# trig_board.net
KiCad netlist of a schematic drawn in EAGLE
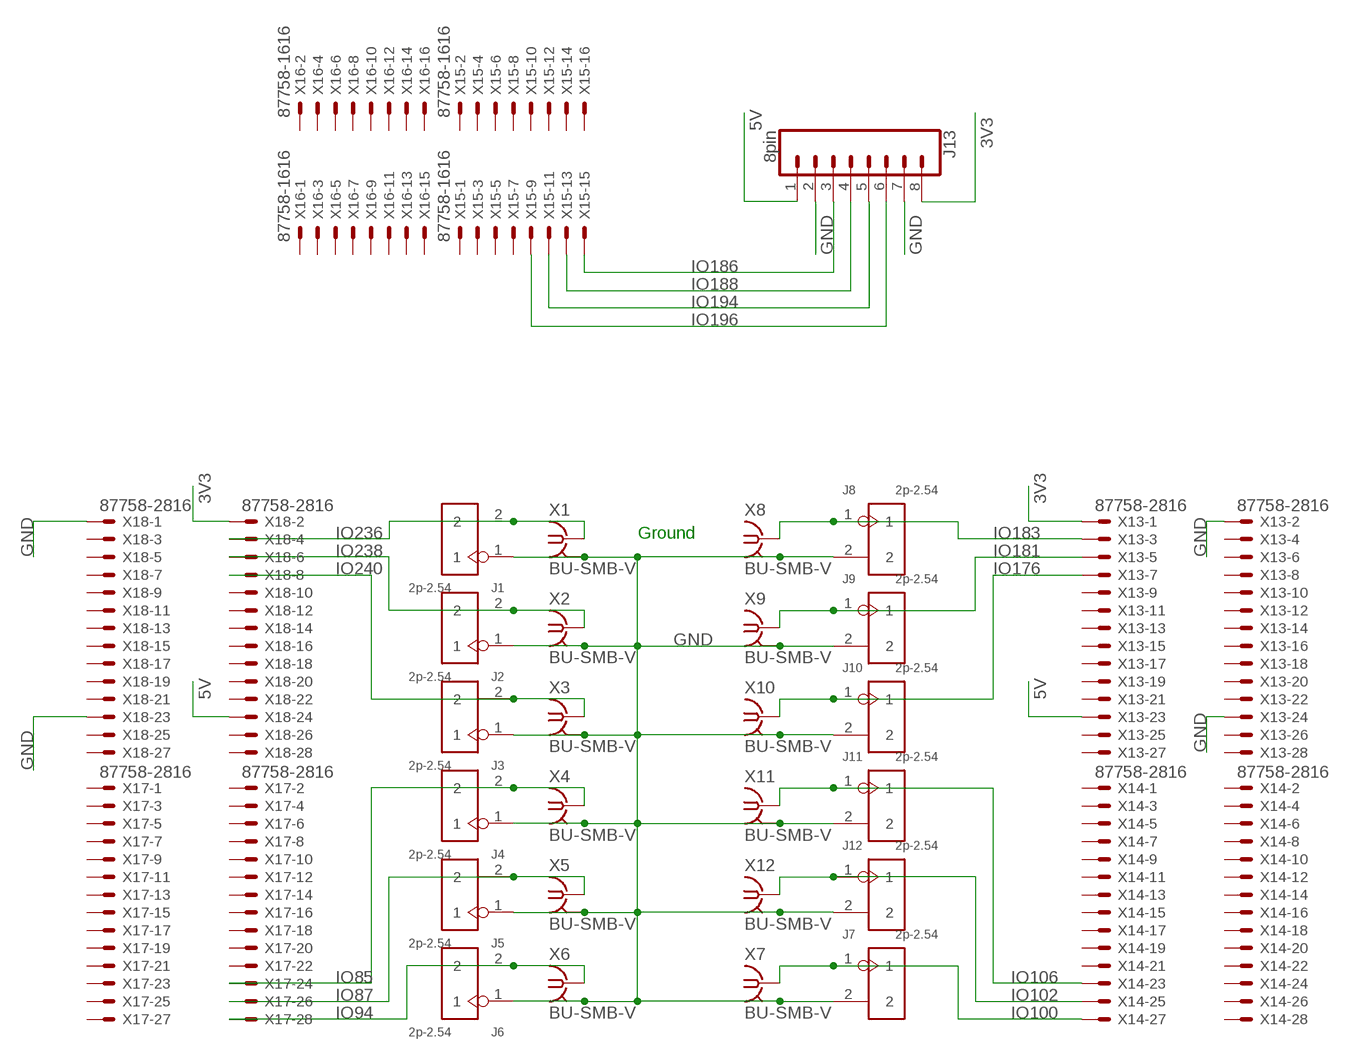
[diagram p0: schematic, sheet 1]

(export (version "E")
  (design (tool "Eeschema 10.0.6"))
  (components
    (comp (ref "J1")
      (value "2p-2.54")
      (footprint "eagle-import:H2-2.54")
      (fields (field (name "MPN") "P125-1102A0BS116A1"))
      (libsource (lib "eagle-import") (part "DIP-BLACK-MALE-HEADER-VERT(2P-2.54)"))
    )
    (comp (ref "J2")
      (value "2p-2.54")
      (footprint "eagle-import:H2-2.54")
      (fields (field (name "MPN") "P125-1102A0BS116A1"))
      (libsource (lib "eagle-import") (part "DIP-BLACK-MALE-HEADER-VERT(2P-2.54)"))
    )
    (comp (ref "J3")
      (value "2p-2.54")
      (footprint "eagle-import:H2-2.54")
      (fields (field (name "MPN") "P125-1102A0BS116A1"))
      (libsource (lib "eagle-import") (part "DIP-BLACK-MALE-HEADER-VERT(2P-2.54)"))
    )
    (comp (ref "J4")
      (value "2p-2.54")
      (footprint "eagle-import:H2-2.54")
      (fields (field (name "MPN") "P125-1102A0BS116A1"))
      (libsource (lib "eagle-import") (part "DIP-BLACK-MALE-HEADER-VERT(2P-2.54)"))
    )
    (comp (ref "J5")
      (value "2p-2.54")
      (footprint "eagle-import:H2-2.54")
      (fields (field (name "MPN") "P125-1102A0BS116A1"))
      (libsource (lib "eagle-import") (part "DIP-BLACK-MALE-HEADER-VERT(2P-2.54)"))
    )
    (comp (ref "J6")
      (value "2p-2.54")
      (footprint "eagle-import:H2-2.54")
      (fields (field (name "MPN") "P125-1102A0BS116A1"))
      (libsource (lib "eagle-import") (part "DIP-BLACK-MALE-HEADER-VERT(2P-2.54)"))
    )
    (comp (ref "J7")
      (value "2p-2.54")
      (footprint "eagle-import:H2-2.54")
      (fields (field (name "MPN") "P125-1102A0BS116A1"))
      (libsource (lib "eagle-import") (part "DIP-BLACK-MALE-HEADER-VERT(2P-2.54)"))
    )
    (comp (ref "J8")
      (value "2p-2.54")
      (footprint "eagle-import:H2-2.54")
      (fields (field (name "MPN") "P125-1102A0BS116A1"))
      (libsource (lib "eagle-import") (part "DIP-BLACK-MALE-HEADER-VERT(2P-2.54)"))
    )
    (comp (ref "J9")
      (value "2p-2.54")
      (footprint "eagle-import:H2-2.54")
      (fields (field (name "MPN") "P125-1102A0BS116A1"))
      (libsource (lib "eagle-import") (part "DIP-BLACK-MALE-HEADER-VERT(2P-2.54)"))
    )
    (comp (ref "J10")
      (value "2p-2.54")
      (footprint "eagle-import:H2-2.54")
      (fields (field (name "MPN") "P125-1102A0BS116A1"))
      (libsource (lib "eagle-import") (part "DIP-BLACK-MALE-HEADER-VERT(2P-2.54)"))
    )
    (comp (ref "J11")
      (value "2p-2.54")
      (footprint "eagle-import:H2-2.54")
      (fields (field (name "MPN") "P125-1102A0BS116A1"))
      (libsource (lib "eagle-import") (part "DIP-BLACK-MALE-HEADER-VERT(2P-2.54)"))
    )
    (comp (ref "J12")
      (value "2p-2.54")
      (footprint "eagle-import:H2-2.54")
      (fields (field (name "MPN") "P125-1102A0BS116A1"))
      (libsource (lib "eagle-import") (part "DIP-BLACK-MALE-HEADER-VERT(2P-2.54)"))
    )
    (comp (ref "J13")
      (value "8pin")
      (footprint "eagle-import:1X08")
      (libsource (lib "eagle-import") (part "CONN_08{dblquote}"))
    )
    (comp (ref "X1")
      (value "BU-SMB-V")
      (footprint "eagle-import:BU-SMB-V")
      (libsource (lib "eagle-import") (part "BU-SMB-V"))
    )
    (comp (ref "X2")
      (value "BU-SMB-V")
      (footprint "eagle-import:BU-SMB-V")
      (libsource (lib "eagle-import") (part "BU-SMB-V"))
    )
    (comp (ref "X3")
      (value "BU-SMB-V")
      (footprint "eagle-import:BU-SMB-V")
      (libsource (lib "eagle-import") (part "BU-SMB-V"))
    )
    (comp (ref "X4")
      (value "BU-SMB-V")
      (footprint "eagle-import:BU-SMB-V")
      (libsource (lib "eagle-import") (part "BU-SMB-V"))
    )
    (comp (ref "X5")
      (value "BU-SMB-V")
      (footprint "eagle-import:BU-SMB-V")
      (libsource (lib "eagle-import") (part "BU-SMB-V"))
    )
    (comp (ref "X6")
      (value "BU-SMB-V")
      (footprint "eagle-import:BU-SMB-V")
      (libsource (lib "eagle-import") (part "BU-SMB-V"))
    )
    (comp (ref "X7")
      (value "BU-SMB-V")
      (footprint "eagle-import:BU-SMB-V")
      (libsource (lib "eagle-import") (part "BU-SMB-V"))
    )
    (comp (ref "X8")
      (value "BU-SMB-V")
      (footprint "eagle-import:BU-SMB-V")
      (libsource (lib "eagle-import") (part "BU-SMB-V"))
    )
    (comp (ref "X9")
      (value "BU-SMB-V")
      (footprint "eagle-import:BU-SMB-V")
      (libsource (lib "eagle-import") (part "BU-SMB-V"))
    )
    (comp (ref "X10")
      (value "BU-SMB-V")
      (footprint "eagle-import:BU-SMB-V")
      (libsource (lib "eagle-import") (part "BU-SMB-V"))
    )
    (comp (ref "X11")
      (value "BU-SMB-V")
      (footprint "eagle-import:BU-SMB-V")
      (libsource (lib "eagle-import") (part "BU-SMB-V"))
    )
    (comp (ref "X12")
      (value "BU-SMB-V")
      (footprint "eagle-import:BU-SMB-V")
      (libsource (lib "eagle-import") (part "BU-SMB-V"))
    )
    (comp (ref "X13")
      (value "87758-2816")
      (footprint "eagle-import:87758-2816")
      (fields (field (name "MF") "MOLEX"))
      (libsource (lib "eagle-import") (part "87758-2816"))
    )
    (comp (ref "X14")
      (value "87758-2816")
      (footprint "eagle-import:87758-2816")
      (fields (field (name "MF") "MOLEX"))
      (libsource (lib "eagle-import") (part "87758-2816"))
    )
    (comp (ref "X15")
      (value "87758-1616")
      (footprint "eagle-import:87758-1616")
      (fields (field (name "MF") "MOLEX"))
      (libsource (lib "eagle-import") (part "87758-1616"))
    )
    (comp (ref "X16")
      (value "87758-1616")
      (footprint "eagle-import:87758-1616")
      (fields (field (name "MF") "MOLEX"))
      (libsource (lib "eagle-import") (part "87758-1616"))
    )
    (comp (ref "X17")
      (value "87758-2816")
      (footprint "eagle-import:87758-2816")
      (fields (field (name "MF") "MOLEX"))
      (libsource (lib "eagle-import") (part "87758-2816"))
    )
    (comp (ref "X18")
      (value "87758-2816")
      (footprint "eagle-import:87758-2816")
      (fields (field (name "MF") "MOLEX"))
      (libsource (lib "eagle-import") (part "87758-2816"))
    )
  )
  (nets
    (net (code "1") (name "/3V3") (class "Default")
      (node (ref "J13") (pin "8") (pinfunction "8_8") (pintype "passive"))
      (node (ref "X13") (pin "1") (pinfunction "S_1") (pintype "passive"))
      (node (ref "X18") (pin "2") (pinfunction "S_2") (pintype "passive"))
    )
    (net (code "2") (name "/5V") (class "Default")
      (node (ref "J13") (pin "1") (pinfunction "1_1") (pintype "passive"))
      (node (ref "X13") (pin "23") (pinfunction "S_23") (pintype "passive"))
      (node (ref "X18") (pin "24") (pinfunction "S_24") (pintype "passive"))
    )
    (net (code "3") (name "/GND") (class "Default")
      (node (ref "J1") (pin "1") (pinfunction "1_1") (pintype "bidirectional"))
      (node (ref "J10") (pin "2") (pinfunction "2_2") (pintype "bidirectional"))
      (node (ref "J11") (pin "2") (pinfunction "2_2") (pintype "bidirectional"))
      (node (ref "J12") (pin "2") (pinfunction "2_2") (pintype "bidirectional"))
      (node (ref "J13") (pin "2") (pinfunction "2_2") (pintype "passive"))
      (node (ref "J13") (pin "7") (pinfunction "7_7") (pintype "passive"))
      (node (ref "J2") (pin "1") (pinfunction "1_1") (pintype "bidirectional"))
      (node (ref "J3") (pin "1") (pinfunction "1_1") (pintype "bidirectional"))
      (node (ref "J4") (pin "1") (pinfunction "1_1") (pintype "bidirectional"))
      (node (ref "J5") (pin "1") (pinfunction "1_1") (pintype "bidirectional"))
      (node (ref "J6") (pin "1") (pinfunction "1_1") (pintype "bidirectional"))
      (node (ref "J7") (pin "2") (pinfunction "2_2") (pintype "bidirectional"))
      (node (ref "J8") (pin "2") (pinfunction "2_2") (pintype "bidirectional"))
      (node (ref "J9") (pin "2") (pinfunction "2_2") (pintype "bidirectional"))
      (node (ref "X1") (pin "2") (pinfunction "2_2") (pintype "passive"))
      (node (ref "X1") (pin "3") (pinfunction "2_3") (pintype "passive"))
      (node (ref "X1") (pin "4") (pinfunction "2_4") (pintype "passive"))
      (node (ref "X1") (pin "5") (pinfunction "2_5") (pintype "passive"))
      (node (ref "X10") (pin "2") (pinfunction "2_2") (pintype "passive"))
      (node (ref "X10") (pin "3") (pinfunction "2_3") (pintype "passive"))
      (node (ref "X10") (pin "4") (pinfunction "2_4") (pintype "passive"))
      (node (ref "X10") (pin "5") (pinfunction "2_5") (pintype "passive"))
      (node (ref "X11") (pin "2") (pinfunction "2_2") (pintype "passive"))
      (node (ref "X11") (pin "3") (pinfunction "2_3") (pintype "passive"))
      (node (ref "X11") (pin "4") (pinfunction "2_4") (pintype "passive"))
      (node (ref "X11") (pin "5") (pinfunction "2_5") (pintype "passive"))
      (node (ref "X12") (pin "2") (pinfunction "2_2") (pintype "passive"))
      (node (ref "X12") (pin "3") (pinfunction "2_3") (pintype "passive"))
      (node (ref "X12") (pin "4") (pinfunction "2_4") (pintype "passive"))
      (node (ref "X12") (pin "5") (pinfunction "2_5") (pintype "passive"))
      (node (ref "X13") (pin "2") (pinfunction "S_2") (pintype "passive"))
      (node (ref "X13") (pin "24") (pinfunction "S_24") (pintype "passive"))
      (node (ref "X18") (pin "1") (pinfunction "S_1") (pintype "passive"))
      (node (ref "X18") (pin "23") (pinfunction "S_23") (pintype "passive"))
      (node (ref "X2") (pin "2") (pinfunction "2_2") (pintype "passive"))
      (node (ref "X2") (pin "3") (pinfunction "2_3") (pintype "passive"))
      (node (ref "X2") (pin "4") (pinfunction "2_4") (pintype "passive"))
      (node (ref "X2") (pin "5") (pinfunction "2_5") (pintype "passive"))
      (node (ref "X3") (pin "2") (pinfunction "2_2") (pintype "passive"))
      (node (ref "X3") (pin "3") (pinfunction "2_3") (pintype "passive"))
      (node (ref "X3") (pin "4") (pinfunction "2_4") (pintype "passive"))
      (node (ref "X3") (pin "5") (pinfunction "2_5") (pintype "passive"))
      (node (ref "X4") (pin "2") (pinfunction "2_2") (pintype "passive"))
      (node (ref "X4") (pin "3") (pinfunction "2_3") (pintype "passive"))
      (node (ref "X4") (pin "4") (pinfunction "2_4") (pintype "passive"))
      (node (ref "X4") (pin "5") (pinfunction "2_5") (pintype "passive"))
      (node (ref "X5") (pin "2") (pinfunction "2_2") (pintype "passive"))
      (node (ref "X5") (pin "3") (pinfunction "2_3") (pintype "passive"))
      (node (ref "X5") (pin "4") (pinfunction "2_4") (pintype "passive"))
      (node (ref "X5") (pin "5") (pinfunction "2_5") (pintype "passive"))
      (node (ref "X6") (pin "2") (pinfunction "2_2") (pintype "passive"))
      (node (ref "X6") (pin "3") (pinfunction "2_3") (pintype "passive"))
      (node (ref "X6") (pin "4") (pinfunction "2_4") (pintype "passive"))
      (node (ref "X6") (pin "5") (pinfunction "2_5") (pintype "passive"))
      (node (ref "X7") (pin "2") (pinfunction "2_2") (pintype "passive"))
      (node (ref "X7") (pin "3") (pinfunction "2_3") (pintype "passive"))
      (node (ref "X7") (pin "4") (pinfunction "2_4") (pintype "passive"))
      (node (ref "X7") (pin "5") (pinfunction "2_5") (pintype "passive"))
      (node (ref "X8") (pin "2") (pinfunction "2_2") (pintype "passive"))
      (node (ref "X8") (pin "3") (pinfunction "2_3") (pintype "passive"))
      (node (ref "X8") (pin "4") (pinfunction "2_4") (pintype "passive"))
      (node (ref "X8") (pin "5") (pinfunction "2_5") (pintype "passive"))
      (node (ref "X9") (pin "2") (pinfunction "2_2") (pintype "passive"))
      (node (ref "X9") (pin "3") (pinfunction "2_3") (pintype "passive"))
      (node (ref "X9") (pin "4") (pinfunction "2_4") (pintype "passive"))
      (node (ref "X9") (pin "5") (pinfunction "2_5") (pintype "passive"))
    )
    (net (code "4") (name "/IO85") (class "Default")
      (node (ref "J4") (pin "2") (pinfunction "2_2") (pintype "bidirectional"))
      (node (ref "X17") (pin "24") (pinfunction "S_24") (pintype "passive"))
      (node (ref "X4") (pin "1") (pinfunction "1_1") (pintype "passive"))
    )
    (net (code "5") (name "/IO87") (class "Default")
      (node (ref "J5") (pin "2") (pinfunction "2_2") (pintype "bidirectional"))
      (node (ref "X17") (pin "26") (pinfunction "S_26") (pintype "passive"))
      (node (ref "X5") (pin "1") (pinfunction "1_1") (pintype "passive"))
    )
    (net (code "6") (name "/IO94") (class "Default")
      (node (ref "J6") (pin "2") (pinfunction "2_2") (pintype "bidirectional"))
      (node (ref "X17") (pin "28") (pinfunction "S_28") (pintype "passive"))
      (node (ref "X6") (pin "1") (pinfunction "1_1") (pintype "passive"))
    )
    (net (code "7") (name "/IO100") (class "Default")
      (node (ref "J7") (pin "1") (pinfunction "1_1") (pintype "bidirectional"))
      (node (ref "X14") (pin "27") (pinfunction "S_27") (pintype "passive"))
      (node (ref "X7") (pin "1") (pinfunction "1_1") (pintype "passive"))
    )
    (net (code "8") (name "/IO102") (class "Default")
      (node (ref "J12") (pin "1") (pinfunction "1_1") (pintype "bidirectional"))
      (node (ref "X12") (pin "1") (pinfunction "1_1") (pintype "passive"))
      (node (ref "X14") (pin "25") (pinfunction "S_25") (pintype "passive"))
    )
    (net (code "9") (name "/IO106") (class "Default")
      (node (ref "J11") (pin "1") (pinfunction "1_1") (pintype "bidirectional"))
      (node (ref "X11") (pin "1") (pinfunction "1_1") (pintype "passive"))
      (node (ref "X14") (pin "23") (pinfunction "S_23") (pintype "passive"))
    )
    (net (code "10") (name "/IO176") (class "Default")
      (node (ref "J10") (pin "1") (pinfunction "1_1") (pintype "bidirectional"))
      (node (ref "X10") (pin "1") (pinfunction "1_1") (pintype "passive"))
      (node (ref "X13") (pin "7") (pinfunction "S_7") (pintype "passive"))
    )
    (net (code "11") (name "/IO181") (class "Default")
      (node (ref "J9") (pin "1") (pinfunction "1_1") (pintype "bidirectional"))
      (node (ref "X13") (pin "5") (pinfunction "S_5") (pintype "passive"))
      (node (ref "X9") (pin "1") (pinfunction "1_1") (pintype "passive"))
    )
    (net (code "12") (name "/IO183") (class "Default")
      (node (ref "J8") (pin "1") (pinfunction "1_1") (pintype "bidirectional"))
      (node (ref "X13") (pin "3") (pinfunction "S_3") (pintype "passive"))
      (node (ref "X8") (pin "1") (pinfunction "1_1") (pintype "passive"))
    )
    (net (code "13") (name "/IO186") (class "Default")
      (node (ref "J13") (pin "3") (pinfunction "3_3") (pintype "passive"))
      (node (ref "X15") (pin "15") (pinfunction "S_15") (pintype "passive"))
    )
    (net (code "14") (name "/IO188") (class "Default")
      (node (ref "J13") (pin "4") (pinfunction "4_4") (pintype "passive"))
      (node (ref "X15") (pin "13") (pinfunction "S_13") (pintype "passive"))
    )
    (net (code "15") (name "/IO194") (class "Default")
      (node (ref "J13") (pin "5") (pinfunction "5_5") (pintype "passive"))
      (node (ref "X15") (pin "11") (pinfunction "S_11") (pintype "passive"))
    )
    (net (code "16") (name "/IO196") (class "Default")
      (node (ref "J13") (pin "6") (pinfunction "6_6") (pintype "passive"))
      (node (ref "X15") (pin "9") (pinfunction "S_9") (pintype "passive"))
    )
    (net (code "17") (name "/IO236") (class "Default")
      (node (ref "J1") (pin "2") (pinfunction "2_2") (pintype "bidirectional"))
      (node (ref "X1") (pin "1") (pinfunction "1_1") (pintype "passive"))
      (node (ref "X18") (pin "4") (pinfunction "S_4") (pintype "passive"))
    )
    (net (code "18") (name "/IO238") (class "Default")
      (node (ref "J2") (pin "2") (pinfunction "2_2") (pintype "bidirectional"))
      (node (ref "X18") (pin "6") (pinfunction "S_6") (pintype "passive"))
      (node (ref "X2") (pin "1") (pinfunction "1_1") (pintype "passive"))
    )
    (net (code "19") (name "/IO240") (class "Default")
      (node (ref "J3") (pin "2") (pinfunction "2_2") (pintype "bidirectional"))
      (node (ref "X18") (pin "8") (pinfunction "S_8") (pintype "passive"))
      (node (ref "X3") (pin "1") (pinfunction "1_1") (pintype "passive"))
    )
    (net (code "20") (name "unconnected-(X13AA-S-Pad8)") (class "Default")
      (node (ref "X13") (pin "8") (pinfunction "S_8") (pintype "passive"))
    )
    (net (code "21") (name "unconnected-(X13AB-S-Pad9)") (class "Default")
      (node (ref "X13") (pin "9") (pinfunction "S_9") (pintype "passive"))
    )
    (net (code "22") (name "unconnected-(X13B-S-Pad10)") (class "Default")
      (node (ref "X13") (pin "10") (pinfunction "S_10") (pintype "passive"))
    )
    (net (code "23") (name "unconnected-(X13C-S-Pad11)") (class "Default")
      (node (ref "X13") (pin "11") (pinfunction "S_11") (pintype "passive"))
    )
    (net (code "24") (name "unconnected-(X13D-S-Pad12)") (class "Default")
      (node (ref "X13") (pin "12") (pinfunction "S_12") (pintype "passive"))
    )
    (net (code "25") (name "unconnected-(X13E-S-Pad13)") (class "Default")
      (node (ref "X13") (pin "13") (pinfunction "S_13") (pintype "passive"))
    )
    (net (code "26") (name "unconnected-(X13F-S-Pad14)") (class "Default")
      (node (ref "X13") (pin "14") (pinfunction "S_14") (pintype "passive"))
    )
    (net (code "27") (name "unconnected-(X13G-S-Pad15)") (class "Default")
      (node (ref "X13") (pin "15") (pinfunction "S_15") (pintype "passive"))
    )
    (net (code "28") (name "unconnected-(X13H-S-Pad16)") (class "Default")
      (node (ref "X13") (pin "16") (pinfunction "S_16") (pintype "passive"))
    )
    (net (code "29") (name "unconnected-(X13I-S-Pad17)") (class "Default")
      (node (ref "X13") (pin "17") (pinfunction "S_17") (pintype "passive"))
    )
    (net (code "30") (name "unconnected-(X13J-S-Pad18)") (class "Default")
      (node (ref "X13") (pin "18") (pinfunction "S_18") (pintype "passive"))
    )
    (net (code "31") (name "unconnected-(X13K-S-Pad19)") (class "Default")
      (node (ref "X13") (pin "19") (pinfunction "S_19") (pintype "passive"))
    )
    (net (code "32") (name "unconnected-(X13M-S-Pad20)") (class "Default")
      (node (ref "X13") (pin "20") (pinfunction "S_20") (pintype "passive"))
    )
    (net (code "33") (name "unconnected-(X13N-S-Pad21)") (class "Default")
      (node (ref "X13") (pin "21") (pinfunction "S_21") (pintype "passive"))
    )
    (net (code "34") (name "unconnected-(X13O-S-Pad22)") (class "Default")
      (node (ref "X13") (pin "22") (pinfunction "S_22") (pintype "passive"))
    )
    (net (code "35") (name "unconnected-(X13R-S-Pad25)") (class "Default")
      (node (ref "X13") (pin "25") (pinfunction "S_25") (pintype "passive"))
    )
    (net (code "36") (name "unconnected-(X13S-S-Pad26)") (class "Default")
      (node (ref "X13") (pin "26") (pinfunction "S_26") (pintype "passive"))
    )
    (net (code "37") (name "unconnected-(X13T-S-Pad27)") (class "Default")
      (node (ref "X13") (pin "27") (pinfunction "S_27") (pintype "passive"))
    )
    (net (code "38") (name "unconnected-(X13U-S-Pad28)") (class "Default")
      (node (ref "X13") (pin "28") (pinfunction "S_28") (pintype "passive"))
    )
    (net (code "39") (name "unconnected-(X13W-S-Pad4)") (class "Default")
      (node (ref "X13") (pin "4") (pinfunction "S_4") (pintype "passive"))
    )
    (net (code "40") (name "unconnected-(X13Y-S-Pad6)") (class "Default")
      (node (ref "X13") (pin "6") (pinfunction "S_6") (pintype "passive"))
    )
    (net (code "41") (name "unconnected-(X14A-S-Pad1)") (class "Default")
      (node (ref "X14") (pin "1") (pinfunction "S_1") (pintype "passive"))
    )
    (net (code "42") (name "unconnected-(X14AA-S-Pad8)") (class "Default")
      (node (ref "X14") (pin "8") (pinfunction "S_8") (pintype "passive"))
    )
    (net (code "43") (name "unconnected-(X14AB-S-Pad9)") (class "Default")
      (node (ref "X14") (pin "9") (pinfunction "S_9") (pintype "passive"))
    )
    (net (code "44") (name "unconnected-(X14B-S-Pad10)") (class "Default")
      (node (ref "X14") (pin "10") (pinfunction "S_10") (pintype "passive"))
    )
    (net (code "45") (name "unconnected-(X14C-S-Pad11)") (class "Default")
      (node (ref "X14") (pin "11") (pinfunction "S_11") (pintype "passive"))
    )
    (net (code "46") (name "unconnected-(X14D-S-Pad12)") (class "Default")
      (node (ref "X14") (pin "12") (pinfunction "S_12") (pintype "passive"))
    )
    (net (code "47") (name "unconnected-(X14E-S-Pad13)") (class "Default")
      (node (ref "X14") (pin "13") (pinfunction "S_13") (pintype "passive"))
    )
    (net (code "48") (name "unconnected-(X14F-S-Pad14)") (class "Default")
      (node (ref "X14") (pin "14") (pinfunction "S_14") (pintype "passive"))
    )
    (net (code "49") (name "unconnected-(X14G-S-Pad15)") (class "Default")
      (node (ref "X14") (pin "15") (pinfunction "S_15") (pintype "passive"))
    )
    (net (code "50") (name "unconnected-(X14H-S-Pad16)") (class "Default")
      (node (ref "X14") (pin "16") (pinfunction "S_16") (pintype "passive"))
    )
    (net (code "51") (name "unconnected-(X14I-S-Pad17)") (class "Default")
      (node (ref "X14") (pin "17") (pinfunction "S_17") (pintype "passive"))
    )
    (net (code "52") (name "unconnected-(X14J-S-Pad18)") (class "Default")
      (node (ref "X14") (pin "18") (pinfunction "S_18") (pintype "passive"))
    )
    (net (code "53") (name "unconnected-(X14K-S-Pad19)") (class "Default")
      (node (ref "X14") (pin "19") (pinfunction "S_19") (pintype "passive"))
    )
    (net (code "54") (name "unconnected-(X14L-S-Pad2)") (class "Default")
      (node (ref "X14") (pin "2") (pinfunction "S_2") (pintype "passive"))
    )
    (net (code "55") (name "unconnected-(X14M-S-Pad20)") (class "Default")
      (node (ref "X14") (pin "20") (pinfunction "S_20") (pintype "passive"))
    )
    (net (code "56") (name "unconnected-(X14N-S-Pad21)") (class "Default")
      (node (ref "X14") (pin "21") (pinfunction "S_21") (pintype "passive"))
    )
    (net (code "57") (name "unconnected-(X14O-S-Pad22)") (class "Default")
      (node (ref "X14") (pin "22") (pinfunction "S_22") (pintype "passive"))
    )
    (net (code "58") (name "unconnected-(X14Q-S-Pad24)") (class "Default")
      (node (ref "X14") (pin "24") (pinfunction "S_24") (pintype "passive"))
    )
    (net (code "59") (name "unconnected-(X14S-S-Pad26)") (class "Default")
      (node (ref "X14") (pin "26") (pinfunction "S_26") (pintype "passive"))
    )
    (net (code "60") (name "unconnected-(X14U-S-Pad28)") (class "Default")
      (node (ref "X14") (pin "28") (pinfunction "S_28") (pintype "passive"))
    )
    (net (code "61") (name "unconnected-(X14V-S-Pad3)") (class "Default")
      (node (ref "X14") (pin "3") (pinfunction "S_3") (pintype "passive"))
    )
    (net (code "62") (name "unconnected-(X14W-S-Pad4)") (class "Default")
      (node (ref "X14") (pin "4") (pinfunction "S_4") (pintype "passive"))
    )
    (net (code "63") (name "unconnected-(X14X-S-Pad5)") (class "Default")
      (node (ref "X14") (pin "5") (pinfunction "S_5") (pintype "passive"))
    )
    (net (code "64") (name "unconnected-(X14Y-S-Pad6)") (class "Default")
      (node (ref "X14") (pin "6") (pinfunction "S_6") (pintype "passive"))
    )
    (net (code "65") (name "unconnected-(X14Z-S-Pad7)") (class "Default")
      (node (ref "X14") (pin "7") (pinfunction "S_7") (pintype "passive"))
    )
    (net (code "66") (name "unconnected-(X15A-S-Pad1)") (class "Default")
      (node (ref "X15") (pin "1") (pinfunction "S_1") (pintype "passive"))
    )
    (net (code "67") (name "unconnected-(X15B-S-Pad10)") (class "Default")
      (node (ref "X15") (pin "10") (pinfunction "S_10") (pintype "passive"))
    )
    (net (code "68") (name "unconnected-(X15D-S-Pad12)") (class "Default")
      (node (ref "X15") (pin "12") (pinfunction "S_12") (pintype "passive"))
    )
    (net (code "69") (name "unconnected-(X15F-S-Pad14)") (class "Default")
      (node (ref "X15") (pin "14") (pinfunction "S_14") (pintype "passive"))
    )
    (net (code "70") (name "unconnected-(X15H-S-Pad16)") (class "Default")
      (node (ref "X15") (pin "16") (pinfunction "S_16") (pintype "passive"))
    )
    (net (code "71") (name "unconnected-(X15I-S-Pad2)") (class "Default")
      (node (ref "X15") (pin "2") (pinfunction "S_2") (pintype "passive"))
    )
    (net (code "72") (name "unconnected-(X15J-S-Pad3)") (class "Default")
      (node (ref "X15") (pin "3") (pinfunction "S_3") (pintype "passive"))
    )
    (net (code "73") (name "unconnected-(X15K-S-Pad4)") (class "Default")
      (node (ref "X15") (pin "4") (pinfunction "S_4") (pintype "passive"))
    )
    (net (code "74") (name "unconnected-(X15L-S-Pad5)") (class "Default")
      (node (ref "X15") (pin "5") (pinfunction "S_5") (pintype "passive"))
    )
    (net (code "75") (name "unconnected-(X15M-S-Pad6)") (class "Default")
      (node (ref "X15") (pin "6") (pinfunction "S_6") (pintype "passive"))
    )
    (net (code "76") (name "unconnected-(X15N-S-Pad7)") (class "Default")
      (node (ref "X15") (pin "7") (pinfunction "S_7") (pintype "passive"))
    )
    (net (code "77") (name "unconnected-(X15O-S-Pad8)") (class "Default")
      (node (ref "X15") (pin "8") (pinfunction "S_8") (pintype "passive"))
    )
    (net (code "78") (name "unconnected-(X16A-S-Pad1)") (class "Default")
      (node (ref "X16") (pin "1") (pinfunction "S_1") (pintype "passive"))
    )
    (net (code "79") (name "unconnected-(X16B-S-Pad10)") (class "Default")
      (node (ref "X16") (pin "10") (pinfunction "S_10") (pintype "passive"))
    )
    (net (code "80") (name "unconnected-(X16C-S-Pad11)") (class "Default")
      (node (ref "X16") (pin "11") (pinfunction "S_11") (pintype "passive"))
    )
    (net (code "81") (name "unconnected-(X16D-S-Pad12)") (class "Default")
      (node (ref "X16") (pin "12") (pinfunction "S_12") (pintype "passive"))
    )
    (net (code "82") (name "unconnected-(X16E-S-Pad13)") (class "Default")
      (node (ref "X16") (pin "13") (pinfunction "S_13") (pintype "passive"))
    )
    (net (code "83") (name "unconnected-(X16F-S-Pad14)") (class "Default")
      (node (ref "X16") (pin "14") (pinfunction "S_14") (pintype "passive"))
    )
    (net (code "84") (name "unconnected-(X16G-S-Pad15)") (class "Default")
      (node (ref "X16") (pin "15") (pinfunction "S_15") (pintype "passive"))
    )
    (net (code "85") (name "unconnected-(X16H-S-Pad16)") (class "Default")
      (node (ref "X16") (pin "16") (pinfunction "S_16") (pintype "passive"))
    )
    (net (code "86") (name "unconnected-(X16I-S-Pad2)") (class "Default")
      (node (ref "X16") (pin "2") (pinfunction "S_2") (pintype "passive"))
    )
    (net (code "87") (name "unconnected-(X16J-S-Pad3)") (class "Default")
      (node (ref "X16") (pin "3") (pinfunction "S_3") (pintype "passive"))
    )
    (net (code "88") (name "unconnected-(X16K-S-Pad4)") (class "Default")
      (node (ref "X16") (pin "4") (pinfunction "S_4") (pintype "passive"))
    )
    (net (code "89") (name "unconnected-(X16L-S-Pad5)") (class "Default")
      (node (ref "X16") (pin "5") (pinfunction "S_5") (pintype "passive"))
    )
    (net (code "90") (name "unconnected-(X16M-S-Pad6)") (class "Default")
      (node (ref "X16") (pin "6") (pinfunction "S_6") (pintype "passive"))
    )
    (net (code "91") (name "unconnected-(X16N-S-Pad7)") (class "Default")
      (node (ref "X16") (pin "7") (pinfunction "S_7") (pintype "passive"))
    )
    (net (code "92") (name "unconnected-(X16O-S-Pad8)") (class "Default")
      (node (ref "X16") (pin "8") (pinfunction "S_8") (pintype "passive"))
    )
    (net (code "93") (name "unconnected-(X16P-S-Pad9)") (class "Default")
      (node (ref "X16") (pin "9") (pinfunction "S_9") (pintype "passive"))
    )
    (net (code "94") (name "unconnected-(X17A-S-Pad1)") (class "Default")
      (node (ref "X17") (pin "1") (pinfunction "S_1") (pintype "passive"))
    )
    (net (code "95") (name "unconnected-(X17AA-S-Pad8)") (class "Default")
      (node (ref "X17") (pin "8") (pinfunction "S_8") (pintype "passive"))
    )
    (net (code "96") (name "unconnected-(X17AB-S-Pad9)") (class "Default")
      (node (ref "X17") (pin "9") (pinfunction "S_9") (pintype "passive"))
    )
    (net (code "97") (name "unconnected-(X17B-S-Pad10)") (class "Default")
      (node (ref "X17") (pin "10") (pinfunction "S_10") (pintype "passive"))
    )
    (net (code "98") (name "unconnected-(X17C-S-Pad11)") (class "Default")
      (node (ref "X17") (pin "11") (pinfunction "S_11") (pintype "passive"))
    )
    (net (code "99") (name "unconnected-(X17D-S-Pad12)") (class "Default")
      (node (ref "X17") (pin "12") (pinfunction "S_12") (pintype "passive"))
    )
    (net (code "100") (name "unconnected-(X17E-S-Pad13)") (class "Default")
      (node (ref "X17") (pin "13") (pinfunction "S_13") (pintype "passive"))
    )
    (net (code "101") (name "unconnected-(X17F-S-Pad14)") (class "Default")
      (node (ref "X17") (pin "14") (pinfunction "S_14") (pintype "passive"))
    )
    (net (code "102") (name "unconnected-(X17G-S-Pad15)") (class "Default")
      (node (ref "X17") (pin "15") (pinfunction "S_15") (pintype "passive"))
    )
    (net (code "103") (name "unconnected-(X17H-S-Pad16)") (class "Default")
      (node (ref "X17") (pin "16") (pinfunction "S_16") (pintype "passive"))
    )
    (net (code "104") (name "unconnected-(X17I-S-Pad17)") (class "Default")
      (node (ref "X17") (pin "17") (pinfunction "S_17") (pintype "passive"))
    )
    (net (code "105") (name "unconnected-(X17J-S-Pad18)") (class "Default")
      (node (ref "X17") (pin "18") (pinfunction "S_18") (pintype "passive"))
    )
    (net (code "106") (name "unconnected-(X17K-S-Pad19)") (class "Default")
      (node (ref "X17") (pin "19") (pinfunction "S_19") (pintype "passive"))
    )
    (net (code "107") (name "unconnected-(X17L-S-Pad2)") (class "Default")
      (node (ref "X17") (pin "2") (pinfunction "S_2") (pintype "passive"))
    )
    (net (code "108") (name "unconnected-(X17M-S-Pad20)") (class "Default")
      (node (ref "X17") (pin "20") (pinfunction "S_20") (pintype "passive"))
    )
    (net (code "109") (name "unconnected-(X17N-S-Pad21)") (class "Default")
      (node (ref "X17") (pin "21") (pinfunction "S_21") (pintype "passive"))
    )
    (net (code "110") (name "unconnected-(X17O-S-Pad22)") (class "Default")
      (node (ref "X17") (pin "22") (pinfunction "S_22") (pintype "passive"))
    )
    (net (code "111") (name "unconnected-(X17P-S-Pad23)") (class "Default")
      (node (ref "X17") (pin "23") (pinfunction "S_23") (pintype "passive"))
    )
    (net (code "112") (name "unconnected-(X17R-S-Pad25)") (class "Default")
      (node (ref "X17") (pin "25") (pinfunction "S_25") (pintype "passive"))
    )
    (net (code "113") (name "unconnected-(X17T-S-Pad27)") (class "Default")
      (node (ref "X17") (pin "27") (pinfunction "S_27") (pintype "passive"))
    )
    (net (code "114") (name "unconnected-(X17V-S-Pad3)") (class "Default")
      (node (ref "X17") (pin "3") (pinfunction "S_3") (pintype "passive"))
    )
    (net (code "115") (name "unconnected-(X17W-S-Pad4)") (class "Default")
      (node (ref "X17") (pin "4") (pinfunction "S_4") (pintype "passive"))
    )
    (net (code "116") (name "unconnected-(X17X-S-Pad5)") (class "Default")
      (node (ref "X17") (pin "5") (pinfunction "S_5") (pintype "passive"))
    )
    (net (code "117") (name "unconnected-(X17Y-S-Pad6)") (class "Default")
      (node (ref "X17") (pin "6") (pinfunction "S_6") (pintype "passive"))
    )
    (net (code "118") (name "unconnected-(X17Z-S-Pad7)") (class "Default")
      (node (ref "X17") (pin "7") (pinfunction "S_7") (pintype "passive"))
    )
    (net (code "119") (name "unconnected-(X18AB-S-Pad9)") (class "Default")
      (node (ref "X18") (pin "9") (pinfunction "S_9") (pintype "passive"))
    )
    (net (code "120") (name "unconnected-(X18B-S-Pad10)") (class "Default")
      (node (ref "X18") (pin "10") (pinfunction "S_10") (pintype "passive"))
    )
    (net (code "121") (name "unconnected-(X18C-S-Pad11)") (class "Default")
      (node (ref "X18") (pin "11") (pinfunction "S_11") (pintype "passive"))
    )
    (net (code "122") (name "unconnected-(X18D-S-Pad12)") (class "Default")
      (node (ref "X18") (pin "12") (pinfunction "S_12") (pintype "passive"))
    )
    (net (code "123") (name "unconnected-(X18E-S-Pad13)") (class "Default")
      (node (ref "X18") (pin "13") (pinfunction "S_13") (pintype "passive"))
    )
    (net (code "124") (name "unconnected-(X18F-S-Pad14)") (class "Default")
      (node (ref "X18") (pin "14") (pinfunction "S_14") (pintype "passive"))
    )
    (net (code "125") (name "unconnected-(X18G-S-Pad15)") (class "Default")
      (node (ref "X18") (pin "15") (pinfunction "S_15") (pintype "passive"))
    )
    (net (code "126") (name "unconnected-(X18H-S-Pad16)") (class "Default")
      (node (ref "X18") (pin "16") (pinfunction "S_16") (pintype "passive"))
    )
    (net (code "127") (name "unconnected-(X18I-S-Pad17)") (class "Default")
      (node (ref "X18") (pin "17") (pinfunction "S_17") (pintype "passive"))
    )
    (net (code "128") (name "unconnected-(X18J-S-Pad18)") (class "Default")
      (node (ref "X18") (pin "18") (pinfunction "S_18") (pintype "passive"))
    )
    (net (code "129") (name "unconnected-(X18K-S-Pad19)") (class "Default")
      (node (ref "X18") (pin "19") (pinfunction "S_19") (pintype "passive"))
    )
    (net (code "130") (name "unconnected-(X18M-S-Pad20)") (class "Default")
      (node (ref "X18") (pin "20") (pinfunction "S_20") (pintype "passive"))
    )
    (net (code "131") (name "unconnected-(X18N-S-Pad21)") (class "Default")
      (node (ref "X18") (pin "21") (pinfunction "S_21") (pintype "passive"))
    )
    (net (code "132") (name "unconnected-(X18O-S-Pad22)") (class "Default")
      (node (ref "X18") (pin "22") (pinfunction "S_22") (pintype "passive"))
    )
    (net (code "133") (name "unconnected-(X18R-S-Pad25)") (class "Default")
      (node (ref "X18") (pin "25") (pinfunction "S_25") (pintype "passive"))
    )
    (net (code "134") (name "unconnected-(X18S-S-Pad26)") (class "Default")
      (node (ref "X18") (pin "26") (pinfunction "S_26") (pintype "passive"))
    )
    (net (code "135") (name "unconnected-(X18T-S-Pad27)") (class "Default")
      (node (ref "X18") (pin "27") (pinfunction "S_27") (pintype "passive"))
    )
    (net (code "136") (name "unconnected-(X18U-S-Pad28)") (class "Default")
      (node (ref "X18") (pin "28") (pinfunction "S_28") (pintype "passive"))
    )
    (net (code "137") (name "unconnected-(X18V-S-Pad3)") (class "Default")
      (node (ref "X18") (pin "3") (pinfunction "S_3") (pintype "passive"))
    )
    (net (code "138") (name "unconnected-(X18X-S-Pad5)") (class "Default")
      (node (ref "X18") (pin "5") (pinfunction "S_5") (pintype "passive"))
    )
    (net (code "139") (name "unconnected-(X18Z-S-Pad7)") (class "Default")
      (node (ref "X18") (pin "7") (pinfunction "S_7") (pintype "passive"))
    )
  )
)
